# MCB-Wise-1570-v2_0_0.net
KiCad netlist of a schematic drawn in EAGLE
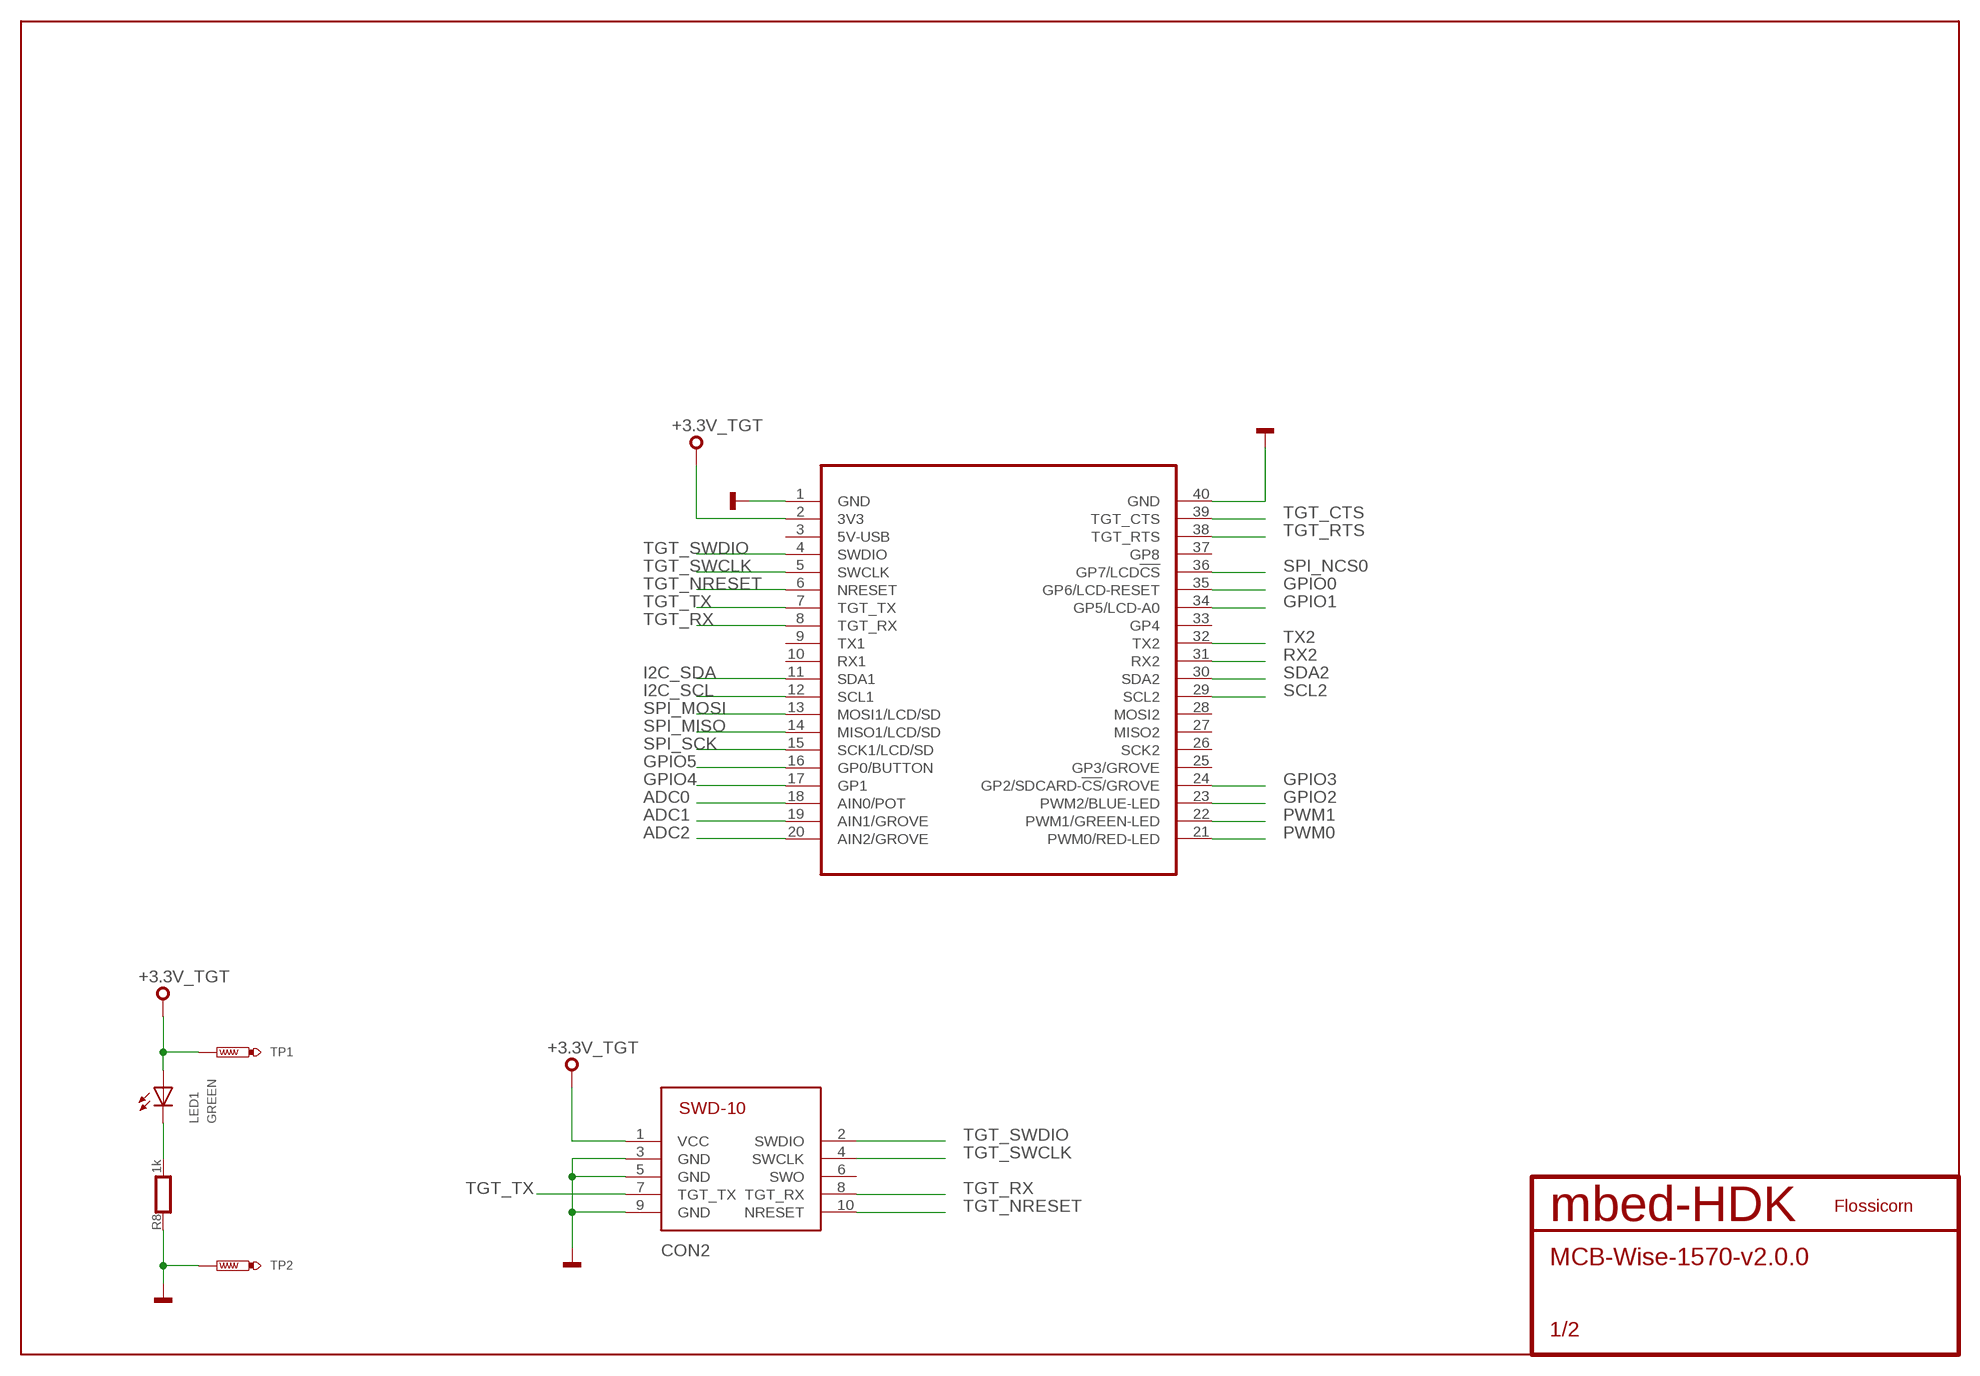
[diagram p0: schematic, sheet 1]
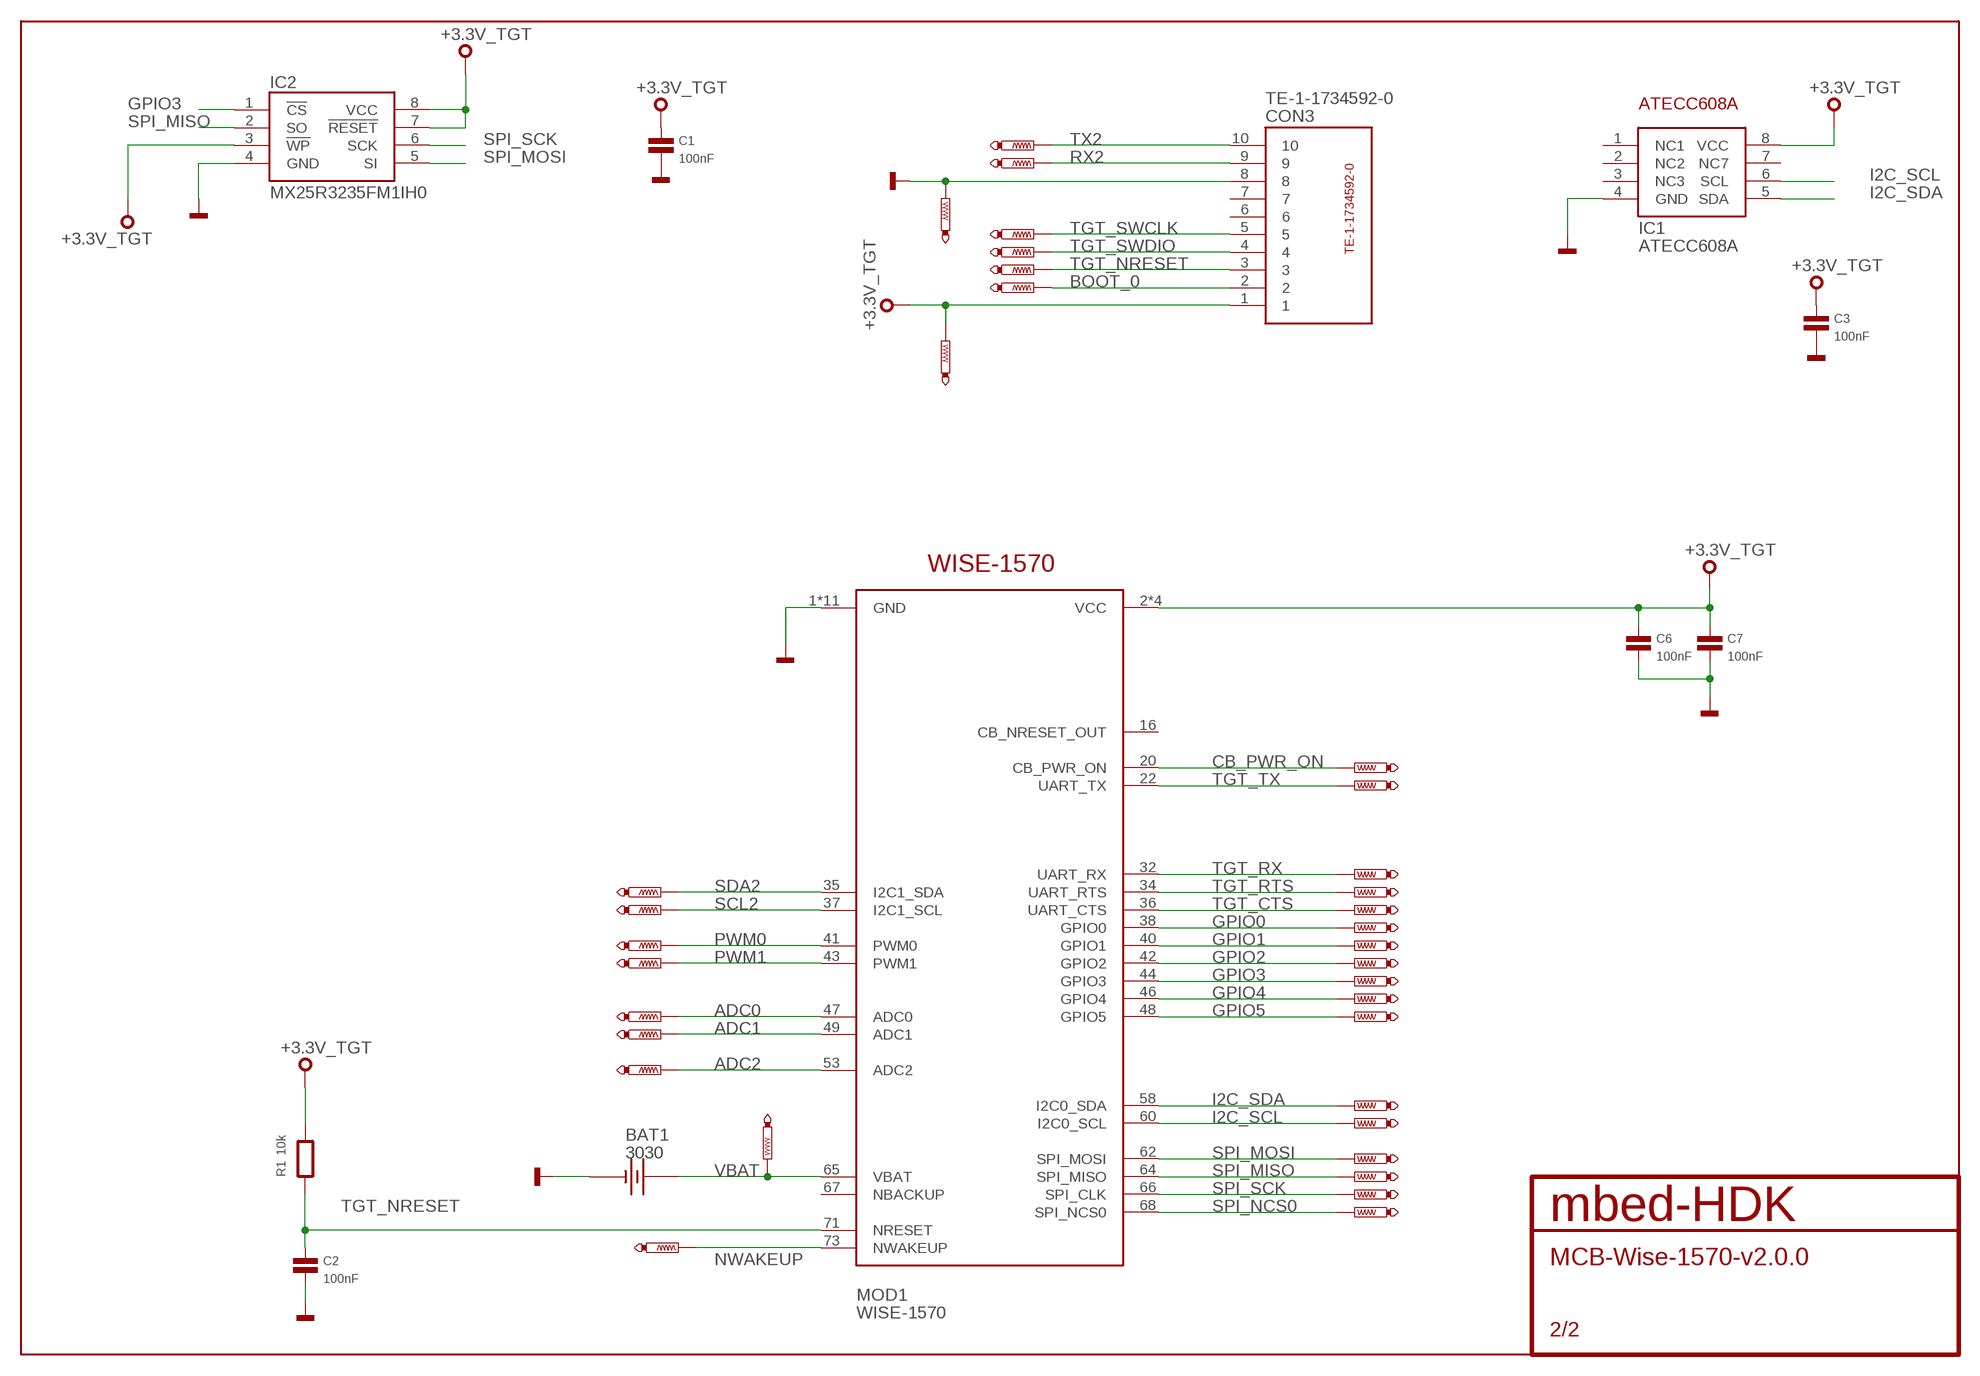
[diagram p1: schematic, sheet 2]

(export (version "E")
  (design (tool "Eeschema 10.0.6"))
  (components
    (comp (ref "BAT1")
      (value "3030")
      (footprint "eagle-import:3030")
      (fields (field (name "MF") "Keystone"))
      (libsource (lib "eagle-import") (part "3030"))
    )
    (comp (ref "C1")
      (value "100nF")
      (footprint "eagle-import:0603")
      (libsource (lib "eagle-import") (part "CAPACITOR0603"))
    )
    (comp (ref "C2")
      (value "100nF")
      (footprint "eagle-import:0603")
      (libsource (lib "eagle-import") (part "CAPACITOR0603"))
    )
    (comp (ref "C3")
      (value "100nF")
      (footprint "eagle-import:0603")
      (libsource (lib "eagle-import") (part "CAPACITOR0603"))
    )
    (comp (ref "C6")
      (value "100nF")
      (footprint "eagle-import:0603")
      (libsource (lib "eagle-import") (part "CAPACITOR0603"))
    )
    (comp (ref "C7")
      (value "100nF")
      (footprint "eagle-import:0603")
      (libsource (lib "eagle-import") (part "CAPACITOR0603"))
    )
    (comp (ref "CON3")
      (value "TE-1-1734592-0")
      (footprint "eagle-import:TE-1-1734592-0")
      (libsource (lib "eagle-import") (part "TE-1-1734592-0"))
    )
    (comp (ref "IC1")
      (value "ATECC608A")
      (footprint "eagle-import:SO8")
      (libsource (lib "eagle-import") (part "ATECC608A"))
    )
    (comp (ref "IC2")
      (value "MX25R3235FM1IH0")
      (footprint "eagle-import:SO8")
      (fields (field (name "MF") "Macronix"))
      (libsource (lib "eagle-import") (part "MX25R3235FM1IH0"))
    )
    (comp (ref "MOD1")
      (value "WISE-1570")
      (footprint "eagle-import:MDT420E02001")
      (libsource (lib "eagle-import") (part "WISE-1570"))
    )
    (comp (ref "R1")
      (value "10k")
      (footprint "eagle-import:0603")
      (libsource (lib "eagle-import") (part "RESISTOR0603"))
    )
    (comp (ref "TP3")
      (value "PTR1TP08R")
      (footprint "eagle-import:TP08R")
      (libsource (lib "eagle-import") (part "PTR1TP08R"))
    )
    (comp (ref "TP4")
      (value "PTR1TP08R")
      (footprint "eagle-import:TP08R")
      (libsource (lib "eagle-import") (part "PTR1TP08R"))
    )
    (comp (ref "TP5")
      (value "PTR1TP08R")
      (footprint "eagle-import:TP08R")
      (libsource (lib "eagle-import") (part "PTR1TP08R"))
    )
    (comp (ref "TP6")
      (value "PTR1TP08R")
      (footprint "eagle-import:TP08R")
      (libsource (lib "eagle-import") (part "PTR1TP08R"))
    )
    (comp (ref "TP7")
      (value "PTR1TP08R")
      (footprint "eagle-import:TP08R")
      (libsource (lib "eagle-import") (part "PTR1TP08R"))
    )
    (comp (ref "TP8")
      (value "PTR1TP08R")
      (footprint "eagle-import:TP08R")
      (libsource (lib "eagle-import") (part "PTR1TP08R"))
    )
    (comp (ref "TP9")
      (value "PTR1TP07R")
      (footprint "eagle-import:TP07R")
      (libsource (lib "eagle-import") (part "PTR1TP07R"))
    )
    (comp (ref "TP10")
      (value "PTR1TP07R")
      (footprint "eagle-import:TP07R")
      (libsource (lib "eagle-import") (part "PTR1TP07R"))
    )
    (comp (ref "TP11")
      (value "PTR1TP07R")
      (footprint "eagle-import:TP07R")
      (libsource (lib "eagle-import") (part "PTR1TP07R"))
    )
    (comp (ref "TP12")
      (value "PTR1TP08R")
      (footprint "eagle-import:TP08R")
      (libsource (lib "eagle-import") (part "PTR1TP08R"))
    )
    (comp (ref "TP13")
      (value "PTR1TP08R")
      (footprint "eagle-import:TP08R")
      (libsource (lib "eagle-import") (part "PTR1TP08R"))
    )
    (comp (ref "TP14")
      (value "PTR1TP07R")
      (footprint "eagle-import:TP07R")
      (libsource (lib "eagle-import") (part "PTR1TP07R"))
    )
    (comp (ref "TP15")
      (value "PTR1TP07R")
      (footprint "eagle-import:TP07R")
      (libsource (lib "eagle-import") (part "PTR1TP07R"))
    )
    (comp (ref "TP16")
      (value "PTR1TP07R")
      (footprint "eagle-import:TP07R")
      (libsource (lib "eagle-import") (part "PTR1TP07R"))
    )
    (comp (ref "TP17")
      (value "PTR1TP07R")
      (footprint "eagle-import:TP07R")
      (libsource (lib "eagle-import") (part "PTR1TP07R"))
    )
    (comp (ref "TP18")
      (value "PTR1TP07R")
      (footprint "eagle-import:TP07R")
      (libsource (lib "eagle-import") (part "PTR1TP07R"))
    )
    (comp (ref "TP19")
      (value "PTR1TP07R")
      (footprint "eagle-import:TP07R")
      (libsource (lib "eagle-import") (part "PTR1TP07R"))
    )
    (comp (ref "TP20")
      (value "PTR1TP07R")
      (footprint "eagle-import:TP07R")
      (libsource (lib "eagle-import") (part "PTR1TP07R"))
    )
    (comp (ref "TP21")
      (value "PTR1TP07R")
      (footprint "eagle-import:TP07R")
      (libsource (lib "eagle-import") (part "PTR1TP07R"))
    )
    (comp (ref "TP22")
      (value "PTR1TP07R")
      (footprint "eagle-import:TP07R")
      (libsource (lib "eagle-import") (part "PTR1TP07R"))
    )
    (comp (ref "TP23")
      (value "PTR1TP07R")
      (footprint "eagle-import:TP07R")
      (libsource (lib "eagle-import") (part "PTR1TP07R"))
    )
    (comp (ref "TP24")
      (value "PTR1TP07R")
      (footprint "eagle-import:TP07R")
      (libsource (lib "eagle-import") (part "PTR1TP07R"))
    )
    (comp (ref "TP25")
      (value "PTR1TP07R")
      (footprint "eagle-import:TP07R")
      (libsource (lib "eagle-import") (part "PTR1TP07R"))
    )
    (comp (ref "TP26")
      (value "PTR1TP07R")
      (footprint "eagle-import:TP07R")
      (libsource (lib "eagle-import") (part "PTR1TP07R"))
    )
    (comp (ref "TP27")
      (value "PTR1TP07R")
      (footprint "eagle-import:TP07R")
      (libsource (lib "eagle-import") (part "PTR1TP07R"))
    )
    (comp (ref "TP28")
      (value "PTR1TP07R")
      (footprint "eagle-import:TP07R")
      (libsource (lib "eagle-import") (part "PTR1TP07R"))
    )
    (comp (ref "TP29")
      (value "PTR1TP07R")
      (footprint "eagle-import:TP07R")
      (libsource (lib "eagle-import") (part "PTR1TP07R"))
    )
    (comp (ref "TP30")
      (value "PTR1TP07R")
      (footprint "eagle-import:TP07R")
      (libsource (lib "eagle-import") (part "PTR1TP07R"))
    )
    (comp (ref "TP31")
      (value "PTR1TP07R")
      (footprint "eagle-import:TP07R")
      (libsource (lib "eagle-import") (part "PTR1TP07R"))
    )
    (comp (ref "TP32")
      (value "PTR1TP07R")
      (footprint "eagle-import:TP07R")
      (libsource (lib "eagle-import") (part "PTR1TP07R"))
    )
    (comp (ref "TP33")
      (value "PTR1TP07R")
      (footprint "eagle-import:TP07R")
      (libsource (lib "eagle-import") (part "PTR1TP07R"))
    )
    (comp (ref "TP34")
      (value "PTR1TP07R")
      (footprint "eagle-import:TP07R")
      (libsource (lib "eagle-import") (part "PTR1TP07R"))
    )
    (comp (ref "TP35")
      (value "PTR1TP07R")
      (footprint "eagle-import:TP07R")
      (libsource (lib "eagle-import") (part "PTR1TP07R"))
    )
    (comp (ref "TP36")
      (value "PTR1TP07R")
      (footprint "eagle-import:TP07R")
      (libsource (lib "eagle-import") (part "PTR1TP07R"))
    )
    (comp (ref "CON2")
      (value "SWD-10/TC2050_SMD")
      (footprint "eagle-import:FTSH-105-02")
      (libsource (lib "eagle-import") (part "SWD-10/TC2050_SMD"))
    )
    (comp (ref "LED1")
      (value "GREEN")
      (footprint "eagle-import:CHIPLED_0603")
      (fields (field (name "MF") "Wurth Electronics Inc"))
      (libsource (lib "eagle-import") (part "SMD_LED0603"))
    )
    (comp (ref "MOD2")
      (value "MODULE_DAUGHTER")
      (footprint "eagle-import:MODULE_DAUGHTER")
      (libsource (lib "eagle-import") (part "MODULE_DAUGHTER"))
    )
    (comp (ref "R8")
      (value "1k")
      (footprint "eagle-import:0603")
      (libsource (lib "eagle-import") (part "RESISTOR0603"))
    )
    (comp (ref "SS1")
      (value "FLOSSICORN0.25")
      (footprint "eagle-import:FLOSSICORN-0.25")
      (libsource (lib "eagle-import") (part "FLOSSICORN0.25"))
    )
    (comp (ref "TP1")
      (value "TEST-POINT-50R-PTH")
      (footprint "eagle-import:TP50-PTH")
      (libsource (lib "eagle-import") (part "TEST-POINT-50R-PTH"))
    )
    (comp (ref "TP2")
      (value "TEST-POINT-50R-PTH")
      (footprint "eagle-import:TP50-PTH")
      (libsource (lib "eagle-import") (part "TEST-POINT-50R-PTH"))
    )
  )
  (nets
    (net (code "1") (name "+3.3V_TGT") (class "Default")
      (node (ref "C1") (pin "1") (pinfunction "P$1_1") (pintype "passive"))
      (node (ref "C3") (pin "1") (pinfunction "P$1_1") (pintype "passive"))
      (node (ref "C6") (pin "1") (pinfunction "P$1_1") (pintype "passive"))
      (node (ref "C7") (pin "1") (pinfunction "P$1_1") (pintype "passive"))
      (node (ref "CON2") (pin "1") (pinfunction "VCC_1") (pintype "bidirectional"))
      (node (ref "CON3") (pin "1") (pinfunction "1_1") (pintype "bidirectional"))
      (node (ref "IC1") (pin "8") (pinfunction "VCC_8") (pintype "bidirectional"))
      (node (ref "IC2") (pin "3") (pinfunction "~{WP}_3") (pintype "bidirectional"))
      (node (ref "IC2") (pin "7") (pinfunction "~{RESET}_7") (pintype "bidirectional"))
      (node (ref "IC2") (pin "8") (pinfunction "VCC_8") (pintype "bidirectional"))
      (node (ref "LED1") (pin "A") (pinfunction "A_A") (pintype "passive"))
      (node (ref "MOD1") (pin "2") (pinfunction "VCC_2") (pintype "bidirectional"))
      (node (ref "MOD1") (pin "4") (pinfunction "VCC_4") (pintype "bidirectional"))
      (node (ref "MOD1") (pin "72") (pinfunction "VCC_72") (pintype "bidirectional"))
      (node (ref "MOD1") (pin "74") (pinfunction "VCC_74") (pintype "bidirectional"))
      (node (ref "MOD2") (pin "2") (pinfunction "3V3_2") (pintype "bidirectional"))
      (node (ref "R1") (pin "2") (pinfunction "P$2_2") (pintype "passive"))
      (node (ref "TP1") (pin "TP") (pinfunction "TP_TP") (pintype "input"))
      (node (ref "TP12") (pin "TP") (pinfunction "TP_TP") (pintype "input"))
    )
    (net (code "2") (name "ADC0") (class "Default")
      (node (ref "MOD1") (pin "47") (pinfunction "ADC0_47") (pintype "bidirectional"))
      (node (ref "MOD2") (pin "18") (pinfunction "AIN0/POT_18") (pintype "bidirectional"))
      (node (ref "TP29") (pin "TP") (pinfunction "TP_TP") (pintype "input"))
    )
    (net (code "3") (name "ADC1") (class "Default")
      (node (ref "MOD1") (pin "49") (pinfunction "ADC1_49") (pintype "bidirectional"))
      (node (ref "MOD2") (pin "19") (pinfunction "AIN1/GROVE_19") (pintype "bidirectional"))
      (node (ref "TP30") (pin "TP") (pinfunction "TP_TP") (pintype "input"))
    )
    (net (code "4") (name "ADC2") (class "Default")
      (node (ref "MOD1") (pin "53") (pinfunction "ADC2_53") (pintype "bidirectional"))
      (node (ref "MOD2") (pin "20") (pinfunction "AIN2/GROVE_20") (pintype "bidirectional"))
      (node (ref "TP31") (pin "TP") (pinfunction "TP_TP") (pintype "input"))
    )
    (net (code "5") (name "BOOT_0") (class "Default")
      (node (ref "CON3") (pin "2") (pinfunction "2_2") (pintype "bidirectional"))
      (node (ref "TP8") (pin "TP") (pinfunction "TP_TP") (pintype "input"))
    )
    (net (code "6") (name "CB_PWR_ON") (class "Default")
      (node (ref "MOD1") (pin "20") (pinfunction "CB_PWR_ON_20") (pintype "bidirectional"))
      (node (ref "TP14") (pin "TP") (pinfunction "TP_TP") (pintype "input"))
    )
    (net (code "7") (name "GND") (class "Default")
      (node (ref "BAT1") (pin "-") (pinfunction "-_-") (pintype "bidirectional"))
      (node (ref "C1") (pin "2") (pinfunction "P$2_2") (pintype "passive"))
      (node (ref "C2") (pin "2") (pinfunction "P$2_2") (pintype "passive"))
      (node (ref "C3") (pin "2") (pinfunction "P$2_2") (pintype "passive"))
      (node (ref "C6") (pin "2") (pinfunction "P$2_2") (pintype "passive"))
      (node (ref "C7") (pin "2") (pinfunction "P$2_2") (pintype "passive"))
      (node (ref "CON2") (pin "3") (pinfunction "GND_3") (pintype "bidirectional"))
      (node (ref "CON2") (pin "5") (pinfunction "GND_5") (pintype "bidirectional"))
      (node (ref "CON2") (pin "9") (pinfunction "GND_9") (pintype "bidirectional"))
      (node (ref "CON3") (pin "8") (pinfunction "8_8") (pintype "bidirectional"))
      (node (ref "IC1") (pin "4") (pinfunction "GND_4") (pintype "bidirectional"))
      (node (ref "IC2") (pin "4") (pinfunction "GND_4") (pintype "bidirectional"))
      (node (ref "MOD1") (pin "1") (pinfunction "GND_1") (pintype "bidirectional"))
      (node (ref "MOD1") (pin "18") (pinfunction "GND_18") (pintype "bidirectional"))
      (node (ref "MOD1") (pin "33") (pinfunction "GND_33") (pintype "bidirectional"))
      (node (ref "MOD1") (pin "39") (pinfunction "GND_39") (pintype "bidirectional"))
      (node (ref "MOD1") (pin "45") (pinfunction "GND_45") (pintype "bidirectional"))
      (node (ref "MOD1") (pin "51") (pinfunction "GND_51") (pintype "bidirectional"))
      (node (ref "MOD1") (pin "57") (pinfunction "GND_57") (pintype "bidirectional"))
      (node (ref "MOD1") (pin "63") (pinfunction "GND_63") (pintype "bidirectional"))
      (node (ref "MOD1") (pin "69") (pinfunction "GND_69") (pintype "bidirectional"))
      (node (ref "MOD1") (pin "7") (pinfunction "GND_7") (pintype "bidirectional"))
      (node (ref "MOD1") (pin "75") (pinfunction "GND_75") (pintype "bidirectional"))
      (node (ref "MOD2") (pin "1") (pinfunction "GND_1") (pintype "bidirectional"))
      (node (ref "MOD2") (pin "40") (pinfunction "GND_40") (pintype "bidirectional"))
      (node (ref "R8") (pin "1") (pinfunction "P$1_1") (pintype "passive"))
      (node (ref "TP13") (pin "TP") (pinfunction "TP_TP") (pintype "input"))
      (node (ref "TP2") (pin "TP") (pinfunction "TP_TP") (pintype "input"))
    )
    (net (code "8") (name "GPIO0") (class "Default")
      (node (ref "MOD1") (pin "38") (pinfunction "GPIO0_38") (pintype "bidirectional"))
      (node (ref "MOD2") (pin "35") (pinfunction "GP6/LCD-RESET_35") (pintype "bidirectional"))
      (node (ref "TP27") (pin "TP") (pinfunction "TP_TP") (pintype "input"))
    )
    (net (code "9") (name "GPIO1") (class "Default")
      (node (ref "MOD1") (pin "40") (pinfunction "GPIO1_40") (pintype "bidirectional"))
      (node (ref "MOD2") (pin "34") (pinfunction "GP5/LCD-A0_34") (pintype "bidirectional"))
      (node (ref "TP26") (pin "TP") (pinfunction "TP_TP") (pintype "input"))
    )
    (net (code "10") (name "GPIO2") (class "Default")
      (node (ref "MOD1") (pin "42") (pinfunction "GPIO2_42") (pintype "bidirectional"))
      (node (ref "MOD2") (pin "23") (pinfunction "PWM2/BLUE-LED_23") (pintype "bidirectional"))
      (node (ref "TP32") (pin "TP") (pinfunction "TP_TP") (pintype "input"))
    )
    (net (code "11") (name "GPIO3") (class "Default")
      (node (ref "IC2") (pin "1") (pinfunction "~{CS}_1") (pintype "bidirectional"))
      (node (ref "MOD1") (pin "44") (pinfunction "GPIO3_44") (pintype "bidirectional"))
      (node (ref "MOD2") (pin "24") (pinfunction "GP2/SDCARD-~{CS}/GROVE_24") (pintype "bidirectional"))
      (node (ref "TP25") (pin "TP") (pinfunction "TP_TP") (pintype "input"))
    )
    (net (code "12") (name "GPIO4") (class "Default")
      (node (ref "MOD1") (pin "46") (pinfunction "GPIO4_46") (pintype "bidirectional"))
      (node (ref "MOD2") (pin "17") (pinfunction "GP1_17") (pintype "bidirectional"))
      (node (ref "TP24") (pin "TP") (pinfunction "TP_TP") (pintype "input"))
    )
    (net (code "13") (name "GPIO5") (class "Default")
      (node (ref "MOD1") (pin "48") (pinfunction "GPIO5_48") (pintype "bidirectional"))
      (node (ref "MOD2") (pin "16") (pinfunction "GP0/BUTTON_16") (pintype "bidirectional"))
      (node (ref "TP23") (pin "TP") (pinfunction "TP_TP") (pintype "input"))
    )
    (net (code "14") (name "I2C_SCL") (class "Default")
      (node (ref "IC1") (pin "6") (pinfunction "SCL_6") (pintype "bidirectional"))
      (node (ref "MOD1") (pin "60") (pinfunction "I2C0_SCL_60") (pintype "bidirectional"))
      (node (ref "MOD2") (pin "12") (pinfunction "SCL1_12") (pintype "bidirectional"))
      (node (ref "TP20") (pin "TP") (pinfunction "TP_TP") (pintype "input"))
    )
    (net (code "15") (name "I2C_SDA") (class "Default")
      (node (ref "IC1") (pin "5") (pinfunction "SDA_5") (pintype "bidirectional"))
      (node (ref "MOD1") (pin "58") (pinfunction "I2C0_SDA_58") (pintype "bidirectional"))
      (node (ref "MOD2") (pin "11") (pinfunction "SDA1_11") (pintype "bidirectional"))
      (node (ref "TP21") (pin "TP") (pinfunction "TP_TP") (pintype "input"))
    )
    (net (code "16") (name "NWAKEUP") (class "Default")
      (node (ref "MOD1") (pin "73") (pinfunction "NWAKEUP_73") (pintype "bidirectional"))
      (node (ref "TP34") (pin "TP") (pinfunction "TP_TP") (pintype "input"))
    )
    (net (code "17") (name "Net-(R8-P$2)") (class "Default")
      (node (ref "LED1") (pin "C") (pinfunction "C_C") (pintype "passive"))
      (node (ref "R8") (pin "2") (pinfunction "P$2_2") (pintype "passive"))
    )
    (net (code "18") (name "PWM0") (class "Default")
      (node (ref "MOD1") (pin "41") (pinfunction "PWM0_41") (pintype "bidirectional"))
      (node (ref "MOD2") (pin "21") (pinfunction "PWM0/RED-LED_21") (pintype "bidirectional"))
      (node (ref "TP16") (pin "TP") (pinfunction "TP_TP") (pintype "input"))
    )
    (net (code "19") (name "PWM1") (class "Default")
      (node (ref "MOD1") (pin "43") (pinfunction "PWM1_43") (pintype "bidirectional"))
      (node (ref "MOD2") (pin "22") (pinfunction "PWM1/GREEN-LED_22") (pintype "bidirectional"))
      (node (ref "TP17") (pin "TP") (pinfunction "TP_TP") (pintype "input"))
    )
    (net (code "20") (name "RX2") (class "Default")
      (node (ref "CON3") (pin "9") (pinfunction "9_9") (pintype "bidirectional"))
      (node (ref "MOD2") (pin "31") (pinfunction "RX2_31") (pintype "bidirectional"))
      (node (ref "TP6") (pin "TP") (pinfunction "TP_TP") (pintype "input"))
    )
    (net (code "21") (name "SCL2") (class "Default")
      (node (ref "MOD1") (pin "37") (pinfunction "I2C1_SCL_37") (pintype "bidirectional"))
      (node (ref "MOD2") (pin "29") (pinfunction "SCL2_29") (pintype "bidirectional"))
      (node (ref "TP36") (pin "TP") (pinfunction "TP_TP") (pintype "input"))
    )
    (net (code "22") (name "SDA2") (class "Default")
      (node (ref "MOD1") (pin "35") (pinfunction "I2C1_SDA_35") (pintype "bidirectional"))
      (node (ref "MOD2") (pin "30") (pinfunction "SDA2_30") (pintype "bidirectional"))
      (node (ref "TP35") (pin "TP") (pinfunction "TP_TP") (pintype "input"))
    )
    (net (code "23") (name "SPI_MISO") (class "Default")
      (node (ref "IC2") (pin "2") (pinfunction "SO_2") (pintype "bidirectional"))
      (node (ref "MOD1") (pin "64") (pinfunction "SPI_MISO_64") (pintype "bidirectional"))
      (node (ref "MOD2") (pin "14") (pinfunction "MISO1/LCD/SD_14") (pintype "bidirectional"))
      (node (ref "TP11") (pin "TP") (pinfunction "TP_TP") (pintype "input"))
    )
    (net (code "24") (name "SPI_MOSI") (class "Default")
      (node (ref "IC2") (pin "5") (pinfunction "SI_5") (pintype "bidirectional"))
      (node (ref "MOD1") (pin "62") (pinfunction "SPI_MOSI_62") (pintype "bidirectional"))
      (node (ref "MOD2") (pin "13") (pinfunction "MOSI1/LCD/SD_13") (pintype "bidirectional"))
      (node (ref "TP22") (pin "TP") (pinfunction "TP_TP") (pintype "input"))
    )
    (net (code "25") (name "SPI_NCS0") (class "Default")
      (node (ref "MOD1") (pin "68") (pinfunction "SPI_NCS0_68") (pintype "bidirectional"))
      (node (ref "MOD2") (pin "36") (pinfunction "GP7/LCD~{CS}_36") (pintype "bidirectional"))
      (node (ref "TP9") (pin "TP") (pinfunction "TP_TP") (pintype "input"))
    )
    (net (code "26") (name "SPI_SCK") (class "Default")
      (node (ref "IC2") (pin "6") (pinfunction "SCK_6") (pintype "bidirectional"))
      (node (ref "MOD1") (pin "66") (pinfunction "SPI_CLK_66") (pintype "bidirectional"))
      (node (ref "MOD2") (pin "15") (pinfunction "SCK1/LCD/SD_15") (pintype "bidirectional"))
      (node (ref "TP10") (pin "TP") (pinfunction "TP_TP") (pintype "input"))
    )
    (net (code "27") (name "TGT_CTS") (class "Default")
      (node (ref "MOD1") (pin "36") (pinfunction "UART_CTS_36") (pintype "bidirectional"))
      (node (ref "MOD2") (pin "39") (pinfunction "TGT_CTS_39") (pintype "bidirectional"))
      (node (ref "TP19") (pin "TP") (pinfunction "TP_TP") (pintype "input"))
    )
    (net (code "28") (name "TGT_NRESET") (class "Default")
      (node (ref "C2") (pin "1") (pinfunction "P$1_1") (pintype "passive"))
      (node (ref "CON2") (pin "10") (pinfunction "NRESET_10") (pintype "bidirectional"))
      (node (ref "CON3") (pin "3") (pinfunction "3_3") (pintype "bidirectional"))
      (node (ref "MOD1") (pin "71") (pinfunction "NRESET_71") (pintype "bidirectional"))
      (node (ref "MOD2") (pin "6") (pinfunction "NRESET_6") (pintype "bidirectional"))
      (node (ref "R1") (pin "1") (pinfunction "P$1_1") (pintype "passive"))
      (node (ref "TP5") (pin "TP") (pinfunction "TP_TP") (pintype "input"))
    )
    (net (code "29") (name "TGT_RTS") (class "Default")
      (node (ref "MOD1") (pin "34") (pinfunction "UART_RTS_34") (pintype "bidirectional"))
      (node (ref "MOD2") (pin "38") (pinfunction "TGT_RTS_38") (pintype "bidirectional"))
      (node (ref "TP18") (pin "TP") (pinfunction "TP_TP") (pintype "input"))
    )
    (net (code "30") (name "TGT_RX") (class "Default")
      (node (ref "CON2") (pin "8") (pinfunction "TGT_RX_8") (pintype "bidirectional"))
      (node (ref "MOD1") (pin "32") (pinfunction "UART_RX_32") (pintype "bidirectional"))
      (node (ref "MOD2") (pin "8") (pinfunction "TGT_RX_8") (pintype "bidirectional"))
      (node (ref "TP28") (pin "TP") (pinfunction "TP_TP") (pintype "input"))
    )
    (net (code "31") (name "TGT_SWCLK") (class "Default")
      (node (ref "CON2") (pin "4") (pinfunction "SWCLK_4") (pintype "bidirectional"))
      (node (ref "CON3") (pin "5") (pinfunction "5_5") (pintype "bidirectional"))
      (node (ref "MOD2") (pin "5") (pinfunction "SWCLK_5") (pintype "bidirectional"))
      (node (ref "TP3") (pin "TP") (pinfunction "TP_TP") (pintype "input"))
    )
    (net (code "32") (name "TGT_SWDIO") (class "Default")
      (node (ref "CON2") (pin "2") (pinfunction "SWDIO_2") (pintype "bidirectional"))
      (node (ref "CON3") (pin "4") (pinfunction "4_4") (pintype "bidirectional"))
      (node (ref "MOD2") (pin "4") (pinfunction "SWDIO_4") (pintype "bidirectional"))
      (node (ref "TP4") (pin "TP") (pinfunction "TP_TP") (pintype "input"))
    )
    (net (code "33") (name "TGT_TX") (class "Default")
      (node (ref "CON2") (pin "7") (pinfunction "TGT_TX_7") (pintype "bidirectional"))
      (node (ref "MOD1") (pin "22") (pinfunction "UART_TX_22") (pintype "bidirectional"))
      (node (ref "MOD2") (pin "7") (pinfunction "TGT_TX_7") (pintype "bidirectional"))
      (node (ref "TP15") (pin "TP") (pinfunction "TP_TP") (pintype "input"))
    )
    (net (code "34") (name "TX2") (class "Default")
      (node (ref "CON3") (pin "10") (pinfunction "10_10") (pintype "bidirectional"))
      (node (ref "MOD2") (pin "32") (pinfunction "TX2_32") (pintype "bidirectional"))
      (node (ref "TP7") (pin "TP") (pinfunction "TP_TP") (pintype "input"))
    )
    (net (code "35") (name "VBAT") (class "Default")
      (node (ref "BAT1") (pin "+1") (pinfunction "+_+1") (pintype "bidirectional"))
      (node (ref "BAT1") (pin "+2") (pinfunction "+_+2") (pintype "bidirectional"))
      (node (ref "MOD1") (pin "65") (pinfunction "VBAT_65") (pintype "bidirectional"))
      (node (ref "TP33") (pin "TP") (pinfunction "TP_TP") (pintype "input"))
    )
    (net (code "36") (name "unconnected-(CON2-SWO-Pad6)") (class "Default")
      (node (ref "CON2") (pin "6") (pinfunction "SWO_6") (pintype "bidirectional"))
    )
    (net (code "37") (name "unconnected-(CON3-Pad6)") (class "Default")
      (node (ref "CON3") (pin "6") (pinfunction "6_6") (pintype "bidirectional"))
    )
    (net (code "38") (name "unconnected-(CON3-Pad7)") (class "Default")
      (node (ref "CON3") (pin "7") (pinfunction "7_7") (pintype "bidirectional"))
    )
    (net (code "39") (name "unconnected-(IC1-NC1-Pad1)") (class "Default")
      (node (ref "IC1") (pin "1") (pinfunction "NC1_1") (pintype "bidirectional"))
    )
    (net (code "40") (name "unconnected-(IC1-NC2-Pad2)") (class "Default")
      (node (ref "IC1") (pin "2") (pinfunction "NC2_2") (pintype "bidirectional"))
    )
    (net (code "41") (name "unconnected-(IC1-NC3-Pad3)") (class "Default")
      (node (ref "IC1") (pin "3") (pinfunction "NC3_3") (pintype "bidirectional"))
    )
    (net (code "42") (name "unconnected-(IC1-NC7-Pad7)") (class "Default")
      (node (ref "IC1") (pin "7") (pinfunction "NC7_7") (pintype "bidirectional"))
    )
    (net (code "43") (name "unconnected-(MOD1-CB_NRESET_OUT-Pad16)") (class "Default")
      (node (ref "MOD1") (pin "16") (pinfunction "CB_NRESET_OUT_16") (pintype "bidirectional"))
    )
    (net (code "44") (name "unconnected-(MOD1-NBACKUP-Pad67)") (class "Default")
      (node (ref "MOD1") (pin "67") (pinfunction "NBACKUP_67") (pintype "bidirectional"))
    )
    (net (code "45") (name "unconnected-(MOD2-5V-USB-Pad3)") (class "Default")
      (node (ref "MOD2") (pin "3") (pinfunction "5V-USB_3") (pintype "bidirectional"))
    )
    (net (code "46") (name "unconnected-(MOD2-GP3{slash}GROVE-Pad25)") (class "Default")
      (node (ref "MOD2") (pin "25") (pinfunction "GP3/GROVE_25") (pintype "bidirectional"))
    )
    (net (code "47") (name "unconnected-(MOD2-GP4-Pad33)") (class "Default")
      (node (ref "MOD2") (pin "33") (pinfunction "GP4_33") (pintype "bidirectional"))
    )
    (net (code "48") (name "unconnected-(MOD2-GP8-Pad37)") (class "Default")
      (node (ref "MOD2") (pin "37") (pinfunction "GP8_37") (pintype "bidirectional"))
    )
    (net (code "49") (name "unconnected-(MOD2-MISO2-Pad27)") (class "Default")
      (node (ref "MOD2") (pin "27") (pinfunction "MISO2_27") (pintype "bidirectional"))
    )
    (net (code "50") (name "unconnected-(MOD2-MOSI2-Pad28)") (class "Default")
      (node (ref "MOD2") (pin "28") (pinfunction "MOSI2_28") (pintype "bidirectional"))
    )
    (net (code "51") (name "unconnected-(MOD2-RX1-Pad10)") (class "Default")
      (node (ref "MOD2") (pin "10") (pinfunction "RX1_10") (pintype "bidirectional"))
    )
    (net (code "52") (name "unconnected-(MOD2-SCK2-Pad26)") (class "Default")
      (node (ref "MOD2") (pin "26") (pinfunction "SCK2_26") (pintype "bidirectional"))
    )
    (net (code "53") (name "unconnected-(MOD2-TX1-Pad9)") (class "Default")
      (node (ref "MOD2") (pin "9") (pinfunction "TX1_9") (pintype "bidirectional"))
    )
  )
)
